# band_pass_filter.net
KiCad netlist of a schematic drawn in EAGLE
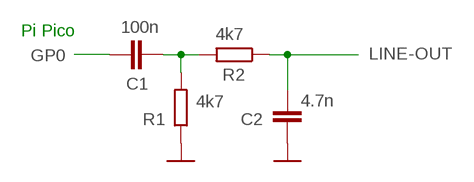
[diagram p0: schematic, sheet 1]

(export (version "E")
  (design (tool "Eeschema 10.0.6"))
  (components
    (comp (ref "C1")
      (value "100n")
      (footprint "eagle-import:C0805")
      (libsource (lib "eagle-import") (part "C"))
    )
    (comp (ref "C2")
      (value "4.7n")
      (footprint "eagle-import:C0805")
      (libsource (lib "eagle-import") (part "C"))
    )
    (comp (ref "R1")
      (value "4k7")
      (footprint "eagle-import:R0805")
      (libsource (lib "eagle-import") (part "R"))
    )
    (comp (ref "R2")
      (value "4k7")
      (footprint "eagle-import:R0805")
      (libsource (lib "eagle-import") (part "R"))
    )
  )
  (nets
    (net (code "1") (name "/GP0") (class "Default")
      (node (ref "C1") (pin "1") (pinfunction "1_1") (pintype "passive"))
    )
    (net (code "2") (name "/LINE-OUT") (class "Default")
      (node (ref "C2") (pin "2") (pinfunction "2_2") (pintype "passive"))
      (node (ref "R2") (pin "1") (pinfunction "1_1") (pintype "passive"))
    )
    (net (code "3") (name "GND") (class "Default")
      (node (ref "C2") (pin "1") (pinfunction "1_1") (pintype "passive"))
      (node (ref "R1") (pin "1") (pinfunction "1_1") (pintype "passive"))
    )
    (net (code "4") (name "Net-(C1-Pad2)") (class "Default")
      (node (ref "C1") (pin "2") (pinfunction "2_2") (pintype "passive"))
      (node (ref "R1") (pin "2") (pinfunction "2_2") (pintype "passive"))
      (node (ref "R2") (pin "2") (pinfunction "2_2") (pintype "passive"))
    )
  )
)
